# Logic_level_converter.net
KiCad netlist of a schematic drawn in EAGLE
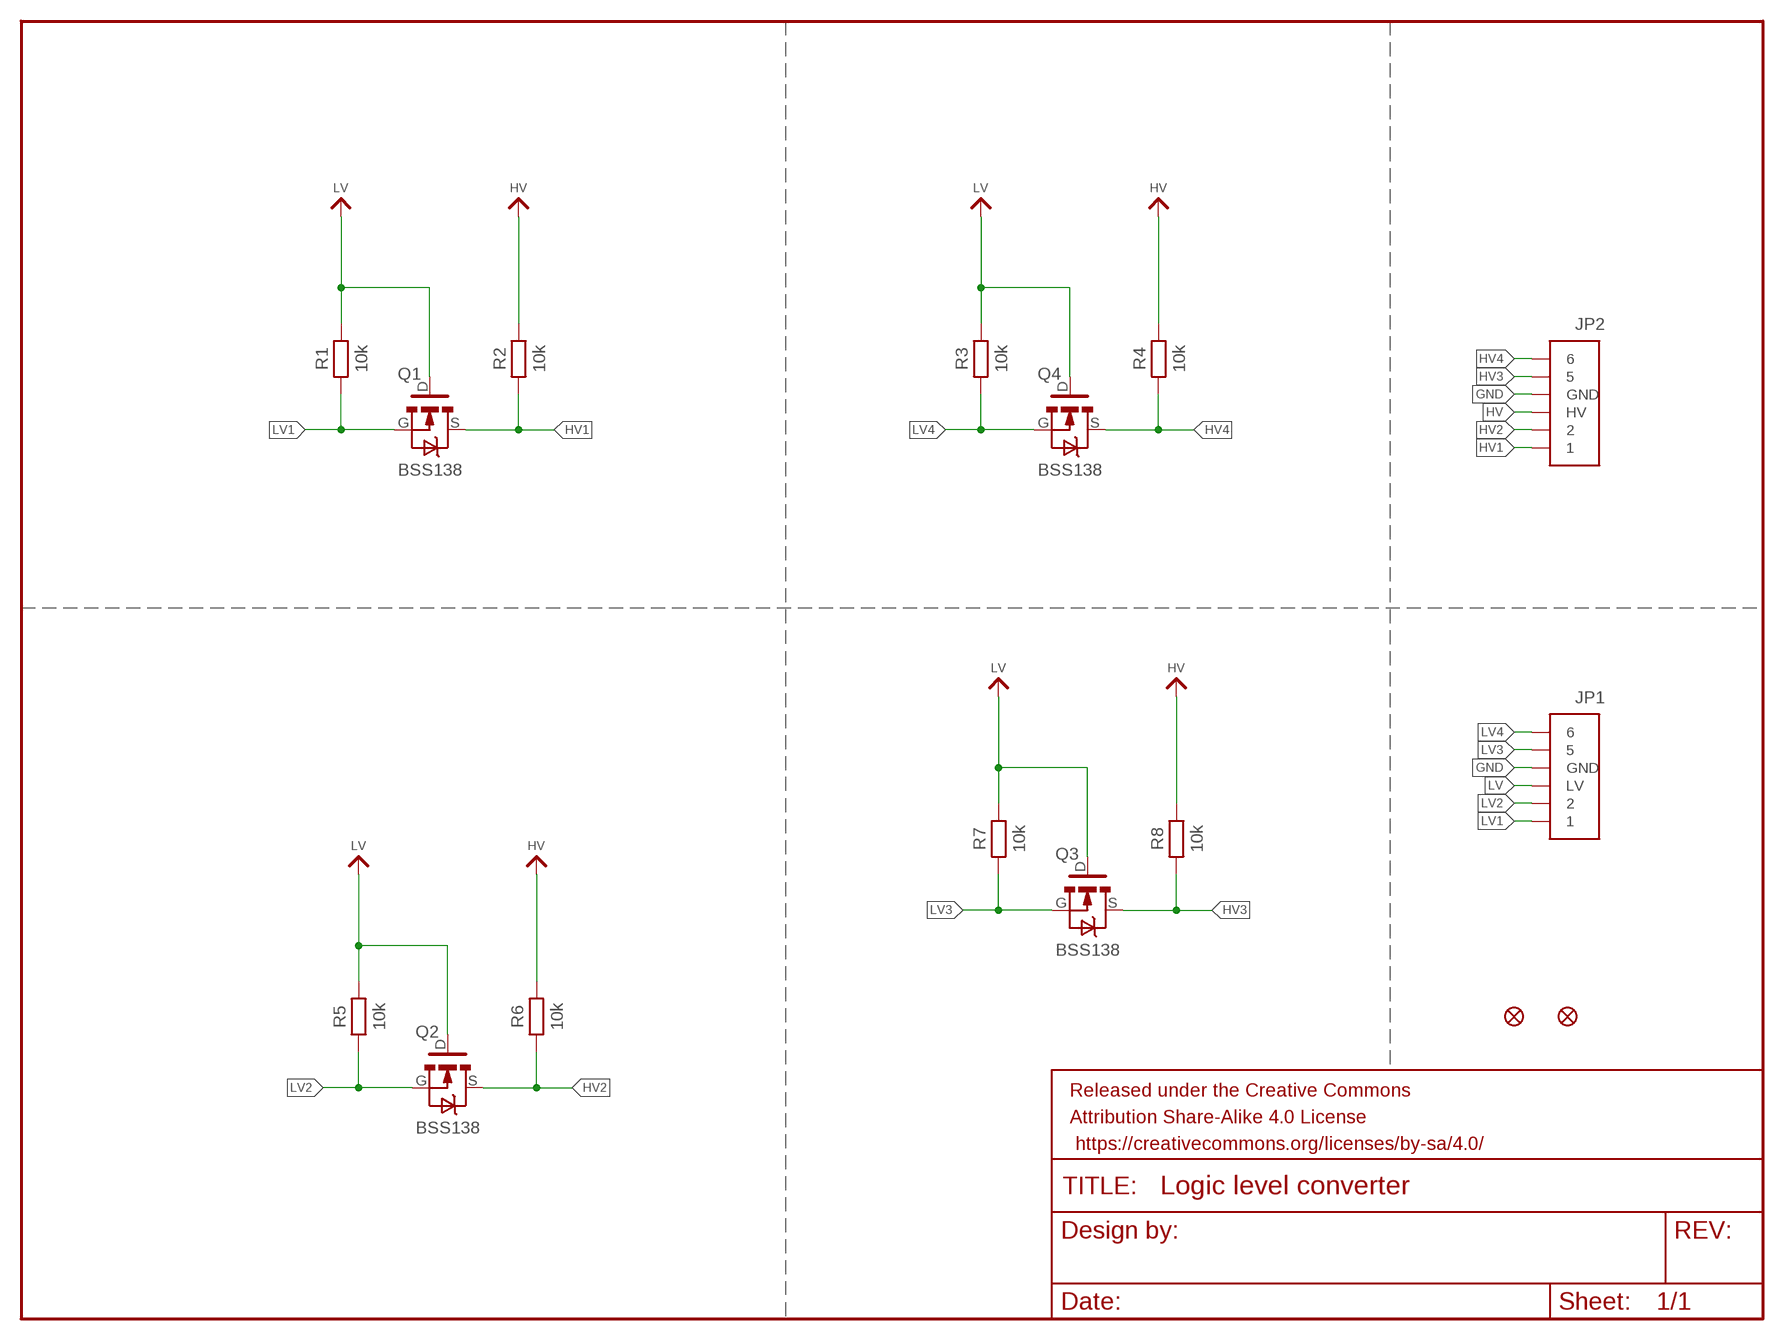
[diagram p0: schematic, sheet 1]

(export (version "E")
  (design (tool "Eeschema 10.0.6"))
  (components
    (comp (ref "FD1")
      (value "FIDUCIAL1X2")
      (footprint "eagle-import:FIDUCIAL-1X2")
      (libsource (lib "eagle-import") (part "FIDUCIAL1X2"))
    )
    (comp (ref "FD2")
      (value "FIDUCIALUFIDUCIAL")
      (footprint "eagle-import:FIDUCIAL-MICRO")
      (libsource (lib "eagle-import") (part "FIDUCIALUFIDUCIAL"))
    )
    (comp (ref "FRAME1")
      (value "FRAME-LETTERNO_PACKAGE")
      (footprint "eagle-import:DUMMY")
      (fields (field (name "DESIGNER") "Nobody"))
      (libsource (lib "eagle-import") (part "FRAME-LETTERNO_PACKAGE"))
    )
    (comp (ref "JP1")
      (value "JUMPER_6PIN_LLC_LV")
      (footprint "eagle-import:JUMPER_6PIN_LLC_LV")
      (libsource (lib "eagle-import") (part "JUMPER_6PIN_LLC_LV"))
    )
    (comp (ref "JP2")
      (value "JUMPER_6PIN_LLC_HV")
      (footprint "eagle-import:JUMPER_6PIN_LLC_HV")
      (libsource (lib "eagle-import") (part "JUMPER_6PIN_LLC_HV"))
    )
    (comp (ref "Q1")
      (value "BSS138")
      (footprint "eagle-import:SOT-23")
      (libsource (lib "eagle-import") (part "BSS138"))
    )
    (comp (ref "Q2")
      (value "BSS138")
      (footprint "eagle-import:SOT-23")
      (libsource (lib "eagle-import") (part "BSS138"))
    )
    (comp (ref "Q3")
      (value "BSS138")
      (footprint "eagle-import:SOT-23")
      (libsource (lib "eagle-import") (part "BSS138"))
    )
    (comp (ref "Q4")
      (value "BSS138")
      (footprint "eagle-import:SOT-23")
      (libsource (lib "eagle-import") (part "BSS138"))
    )
    (comp (ref "R1")
      (value "10k")
      (footprint "eagle-import:0603_RESISTOR")
      (libsource (lib "eagle-import") (part "0603_RESISTOR"))
    )
    (comp (ref "R2")
      (value "10k")
      (footprint "eagle-import:0603_RESISTOR")
      (libsource (lib "eagle-import") (part "0603_RESISTOR"))
    )
    (comp (ref "R3")
      (value "10k")
      (footprint "eagle-import:0603_RESISTOR")
      (libsource (lib "eagle-import") (part "0603_RESISTOR"))
    )
    (comp (ref "R4")
      (value "10k")
      (footprint "eagle-import:0603_RESISTOR")
      (libsource (lib "eagle-import") (part "0603_RESISTOR"))
    )
    (comp (ref "R5")
      (value "10k")
      (footprint "eagle-import:0603_RESISTOR")
      (libsource (lib "eagle-import") (part "0603_RESISTOR"))
    )
    (comp (ref "R6")
      (value "10k")
      (footprint "eagle-import:0603_RESISTOR")
      (libsource (lib "eagle-import") (part "0603_RESISTOR"))
    )
    (comp (ref "R7")
      (value "10k")
      (footprint "eagle-import:0603_RESISTOR")
      (libsource (lib "eagle-import") (part "0603_RESISTOR"))
    )
    (comp (ref "R8")
      (value "10k")
      (footprint "eagle-import:0603_RESISTOR")
      (libsource (lib "eagle-import") (part "0603_RESISTOR"))
    )
  )
  (nets
    (net (code "1") (name "GND") (class "Default")
      (node (ref "JP1") (pin "GND") (pinfunction "GND_GND") (pintype "bidirectional"))
      (node (ref "JP2") (pin "GND") (pinfunction "GND_GND") (pintype "bidirectional"))
    )
    (net (code "2") (name "HV") (class "Default")
      (node (ref "JP2") (pin "HV") (pinfunction "HV_HV") (pintype "bidirectional"))
      (node (ref "R2") (pin "P$2") (pinfunction "P$2_P$2") (pintype "bidirectional"))
      (node (ref "R4") (pin "P$2") (pinfunction "P$2_P$2") (pintype "bidirectional"))
      (node (ref "R6") (pin "P$2") (pinfunction "P$2_P$2") (pintype "bidirectional"))
      (node (ref "R8") (pin "P$2") (pinfunction "P$2_P$2") (pintype "bidirectional"))
    )
    (net (code "3") (name "HV1") (class "Default")
      (node (ref "JP2") (pin "1") (pinfunction "1_1") (pintype "bidirectional"))
      (node (ref "Q1") (pin "S") (pinfunction "S_S") (pintype "bidirectional"))
      (node (ref "R2") (pin "P$1") (pinfunction "P$1_P$1") (pintype "bidirectional"))
    )
    (net (code "4") (name "HV2") (class "Default")
      (node (ref "JP2") (pin "2") (pinfunction "2_2") (pintype "bidirectional"))
      (node (ref "Q2") (pin "S") (pinfunction "S_S") (pintype "bidirectional"))
      (node (ref "R6") (pin "P$1") (pinfunction "P$1_P$1") (pintype "bidirectional"))
    )
    (net (code "5") (name "HV3") (class "Default")
      (node (ref "JP2") (pin "5") (pinfunction "5_5") (pintype "bidirectional"))
      (node (ref "Q3") (pin "S") (pinfunction "S_S") (pintype "bidirectional"))
      (node (ref "R8") (pin "P$1") (pinfunction "P$1_P$1") (pintype "bidirectional"))
    )
    (net (code "6") (name "HV4") (class "Default")
      (node (ref "JP2") (pin "6") (pinfunction "6_6") (pintype "bidirectional"))
      (node (ref "Q4") (pin "S") (pinfunction "S_S") (pintype "bidirectional"))
      (node (ref "R4") (pin "P$1") (pinfunction "P$1_P$1") (pintype "bidirectional"))
    )
    (net (code "7") (name "LV") (class "Default")
      (node (ref "JP1") (pin "LV") (pinfunction "LV_LV") (pintype "bidirectional"))
      (node (ref "Q1") (pin "D") (pinfunction "D_D") (pintype "bidirectional"))
      (node (ref "Q2") (pin "D") (pinfunction "D_D") (pintype "bidirectional"))
      (node (ref "Q3") (pin "D") (pinfunction "D_D") (pintype "bidirectional"))
      (node (ref "Q4") (pin "D") (pinfunction "D_D") (pintype "bidirectional"))
      (node (ref "R1") (pin "P$2") (pinfunction "P$2_P$2") (pintype "bidirectional"))
      (node (ref "R3") (pin "P$2") (pinfunction "P$2_P$2") (pintype "bidirectional"))
      (node (ref "R5") (pin "P$2") (pinfunction "P$2_P$2") (pintype "bidirectional"))
      (node (ref "R7") (pin "P$2") (pinfunction "P$2_P$2") (pintype "bidirectional"))
    )
    (net (code "8") (name "LV1") (class "Default")
      (node (ref "JP1") (pin "1") (pinfunction "1_1") (pintype "bidirectional"))
      (node (ref "Q1") (pin "G") (pinfunction "G_G") (pintype "bidirectional"))
      (node (ref "R1") (pin "P$1") (pinfunction "P$1_P$1") (pintype "bidirectional"))
    )
    (net (code "9") (name "LV2") (class "Default")
      (node (ref "JP1") (pin "2") (pinfunction "2_2") (pintype "bidirectional"))
      (node (ref "Q2") (pin "G") (pinfunction "G_G") (pintype "bidirectional"))
      (node (ref "R5") (pin "P$1") (pinfunction "P$1_P$1") (pintype "bidirectional"))
    )
    (net (code "10") (name "LV3") (class "Default")
      (node (ref "JP1") (pin "5") (pinfunction "5_5") (pintype "bidirectional"))
      (node (ref "Q3") (pin "G") (pinfunction "G_G") (pintype "bidirectional"))
      (node (ref "R7") (pin "P$1") (pinfunction "P$1_P$1") (pintype "bidirectional"))
    )
    (net (code "11") (name "LV4") (class "Default")
      (node (ref "JP1") (pin "6") (pinfunction "6_6") (pintype "bidirectional"))
      (node (ref "Q4") (pin "G") (pinfunction "G_G") (pintype "bidirectional"))
      (node (ref "R3") (pin "P$1") (pinfunction "P$1_P$1") (pintype "bidirectional"))
    )
  )
)
